# GSM_LED_Driver.net
KiCad netlist of a schematic drawn in Altium Designer
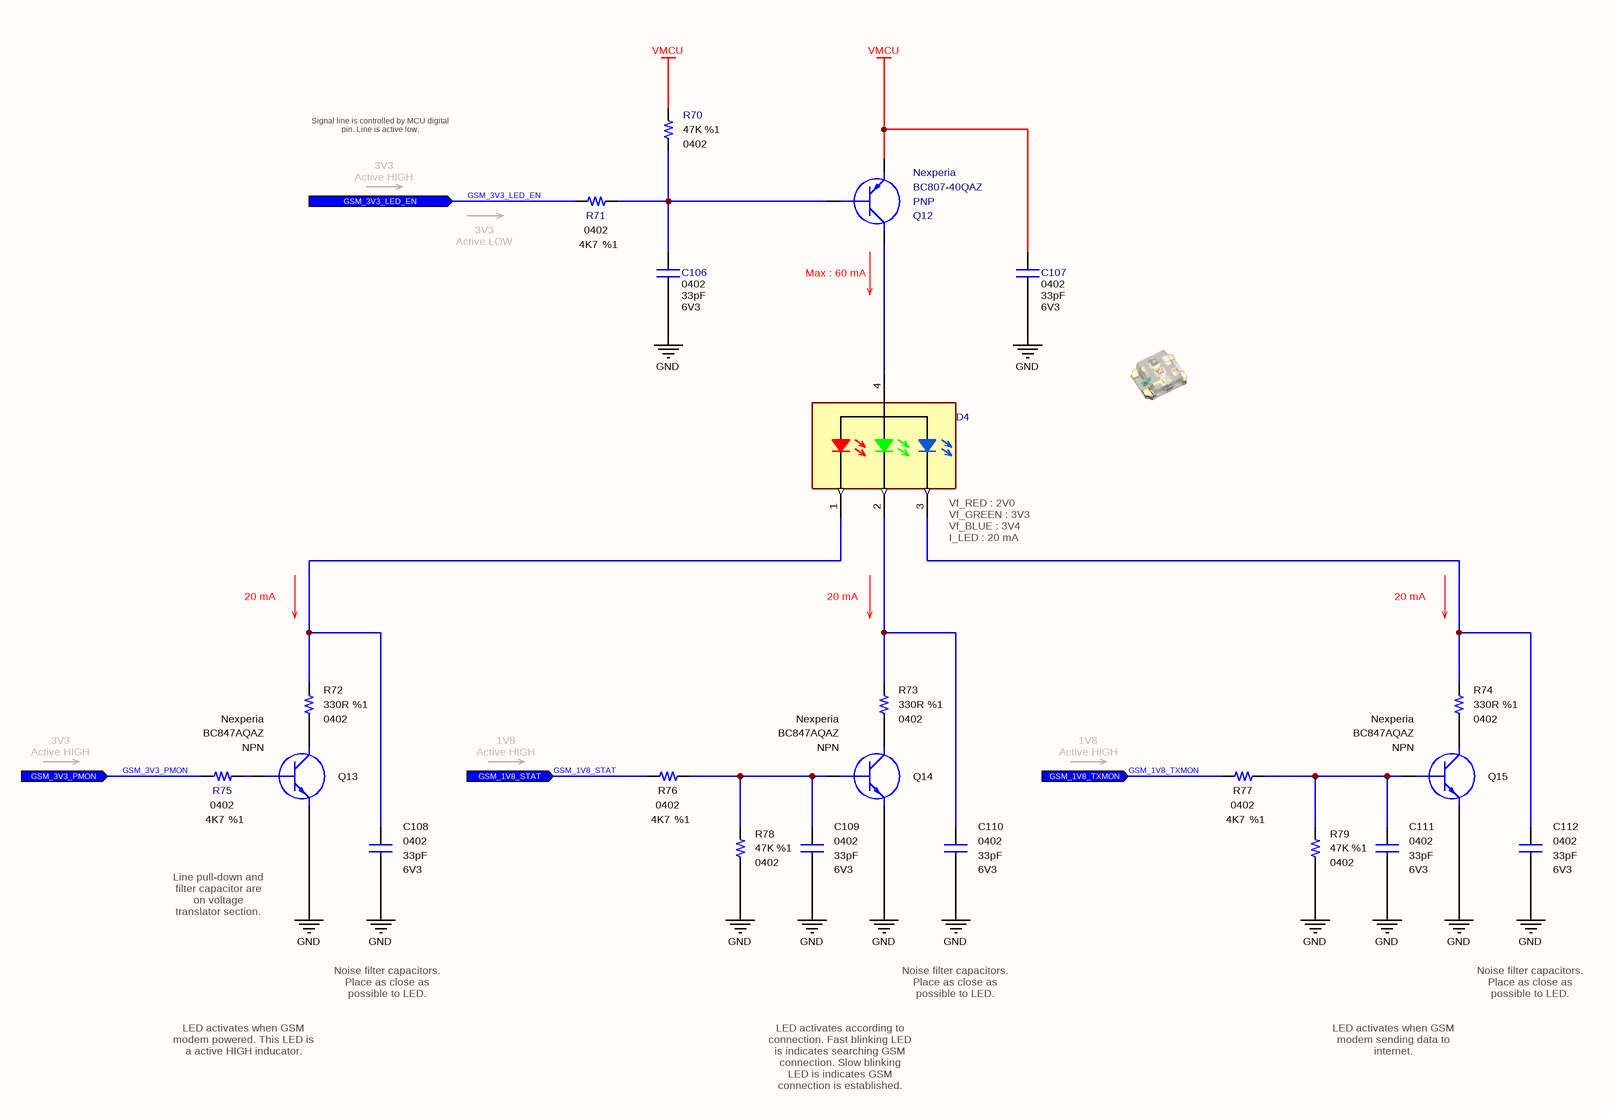
[diagram p0: GSM LED Driver.SchDoc]

(export (version "E")
  (design (tool "Eeschema 10.0.6"))
  (components
    (comp (ref "C106")
      (value "33pF")
      (footprint "CAPACITOR_0402")
      (description "Capacitor - 33pF [0402] (Ceramic)")
      (fields
        (field (name "CASE") "0402")
        (field (name "TOLERANCE") "10%")
        (field (name "VOLTAGE") "6V3")
        (field (name "MANUFACTURER PART NUMBER") "C0402C330J9RACAUTO")
      )
      (libsource (lib "Ovoo_Library") (part "Capacitor - 33pF [0402-6V3]"))
    )
    (comp (ref "C107")
      (value "33pF")
      (footprint "CAPACITOR_0402")
      (description "Capacitor - 33pF [0402] (Ceramic)")
      (fields
        (field (name "CASE") "0402")
        (field (name "TOLERANCE") "10%")
        (field (name "VOLTAGE") "6V3")
        (field (name "MANUFACTURER PART NUMBER") "C0402C330J9RACAUTO")
      )
      (libsource (lib "Ovoo_Library") (part "Capacitor - 33pF [0402-6V3]"))
    )
    (comp (ref "C108")
      (value "33pF")
      (footprint "CAPACITOR_0402")
      (description "Capacitor - 33pF [0402] (Ceramic)")
      (fields
        (field (name "CASE") "0402")
        (field (name "TOLERANCE") "10%")
        (field (name "VOLTAGE") "6V3")
        (field (name "MANUFACTURER PART NUMBER") "C0402C330J9RACAUTO")
      )
      (libsource (lib "Ovoo_Library") (part "Capacitor - 33pF [0402-6V3]"))
    )
    (comp (ref "C109")
      (value "33pF")
      (footprint "CAPACITOR_0402")
      (description "Capacitor - 33pF [0402] (Ceramic)")
      (fields
        (field (name "CASE") "0402")
        (field (name "TOLERANCE") "10%")
        (field (name "VOLTAGE") "6V3")
        (field (name "MANUFACTURER PART NUMBER") "C0402C330J9RACAUTO")
      )
      (libsource (lib "Ovoo_Library") (part "Capacitor - 33pF [0402-6V3]"))
    )
    (comp (ref "C110")
      (value "33pF")
      (footprint "CAPACITOR_0402")
      (description "Capacitor - 33pF [0402] (Ceramic)")
      (fields
        (field (name "CASE") "0402")
        (field (name "TOLERANCE") "10%")
        (field (name "VOLTAGE") "6V3")
        (field (name "MANUFACTURER PART NUMBER") "C0402C330J9RACAUTO")
      )
      (libsource (lib "Ovoo_Library") (part "Capacitor - 33pF [0402-6V3]"))
    )
    (comp (ref "C111")
      (value "33pF")
      (footprint "CAPACITOR_0402")
      (description "Capacitor - 33pF [0402] (Ceramic)")
      (fields
        (field (name "CASE") "0402")
        (field (name "TOLERANCE") "10%")
        (field (name "VOLTAGE") "6V3")
        (field (name "MANUFACTURER PART NUMBER") "C0402C330J9RACAUTO")
      )
      (libsource (lib "Ovoo_Library") (part "Capacitor - 33pF [0402-6V3]"))
    )
    (comp (ref "C112")
      (value "33pF")
      (footprint "CAPACITOR_0402")
      (description "Capacitor - 33pF [0402] (Ceramic)")
      (fields
        (field (name "CASE") "0402")
        (field (name "TOLERANCE") "10%")
        (field (name "VOLTAGE") "6V3")
        (field (name "MANUFACTURER PART NUMBER") "C0402C330J9RACAUTO")
      )
      (libsource (lib "Ovoo_Library") (part "Capacitor - 33pF [0402-6V3]"))
    )
    (comp (ref "D4")
      (value "150066M153000")
      (footprint "Wurth_0606")
      (description "Standard LEDs - SMD PICOLED series Red LED")
      (fields (field (name "MOUSER PART NUMBER") "710-150066M153000"))
      (libsource (lib "Ovoo_Library") (part "Diode - RGB LED (150066M153000)"))
    )
    (comp (ref "Q12")
      (value "Bipolar PNP Transistors")
      (footprint "SOT1215")
      (description "Bipolar Transistors - BJT 45 V, 500 mA PNP gen purpose transistors")
      (fields
        (field (name "MOUSER PART NUMBER") "771-BC807-40QAZ")
        (field (name "POLARITY") "PNP")
        (field (name "MANUFACTURER NAME") "Nexperia")
        (field (name "MANUFACTURER PART NUMBER") "BC807-40QAZ")
      )
      (libsource (lib "Ovoo_Library") (part "Transistor - BC807"))
    )
    (comp (ref "Q13")
      (value "BC847AQAZ")
      (footprint "SOT1215")
      (description "Bipolar NPN Transistors")
      (fields
        (field (name "POLARITY") "NPN")
        (field (name "MANUFACTURER NAME") "Nexperia")
        (field (name "MANUFACTURER PART NUMBER") "BC847AQAZ")
      )
      (libsource (lib "Ovoo_Library") (part "Transistor - BC847"))
    )
    (comp (ref "Q14")
      (value "BC847AQAZ")
      (footprint "SOT1215")
      (description "Bipolar NPN Transistors")
      (fields
        (field (name "POLARITY") "NPN")
        (field (name "MANUFACTURER NAME") "Nexperia")
        (field (name "MANUFACTURER PART NUMBER") "BC847AQAZ")
      )
      (libsource (lib "Ovoo_Library") (part "Transistor - BC847"))
    )
    (comp (ref "Q15")
      (value "BC847AQAZ")
      (footprint "SOT1215")
      (description "Bipolar NPN Transistors")
      (fields
        (field (name "POLARITY") "NPN")
        (field (name "MANUFACTURER NAME") "Nexperia")
        (field (name "MANUFACTURER PART NUMBER") "BC847AQAZ")
      )
      (libsource (lib "Ovoo_Library") (part "Transistor - BC847"))
    )
    (comp (ref "R70")
      (value "47K")
      (footprint "RESISTOR_0402")
      (description "Thick Film Resistors - SMD 1/16 W 47 Kohms 1%")
      (fields
        (field (name "TOLERANCE") "%1")
        (field (name "CASE") "0402")
        (field (name "MANUFACTURER PART NUMBER") "CRCW040247K0FKED")
        (field (name "Comment") "47K - 0402 - %1 - 1/16W")
      )
      (libsource (lib "Ovoo_Library") (part "Resistor - 47K"))
    )
    (comp (ref "R71")
      (value "4K7")
      (footprint "RESISTOR_0402")
      (description "Thick Film Resistors - SMD 1/16 W 4.7 Kohms 1%")
      (fields
        (field (name "MANUFACTURER PART NUMBER") "CRCW04024K70FKED")
        (field (name "MOUSER PART NUMBER") "71-CRCW0402-4.7K-E3")
        (field (name "TOLERANCE") "%1")
        (field (name "CASE") "0402")
      )
      (libsource (lib "Ovoo_Library") (part "Resistor - 4K7"))
    )
    (comp (ref "R72")
      (value "330R")
      (footprint "RESISTOR_0402")
      (description "Thick Film Resistors - SMD 1/16 W 330 Ohm 1%")
      (fields
        (field (name "MANUFACTURER PART NUMBER") "CRCW0402330RFKED")
        (field (name "MOUSER PART NUMBER") "71-CRCW0402-330-E3")
        (field (name "CASE") "0402")
        (field (name "TOLERANCE") "%1")
      )
      (libsource (lib "Ovoo_Library") (part "Resistor - 330R"))
    )
    (comp (ref "R73")
      (value "330R")
      (footprint "RESISTOR_0402")
      (description "Thick Film Resistors - SMD 1/16 W 330 Ohm 1%")
      (fields
        (field (name "MANUFACTURER PART NUMBER") "CRCW0402330RFKED")
        (field (name "MOUSER PART NUMBER") "71-CRCW0402-330-E3")
        (field (name "CASE") "0402")
        (field (name "TOLERANCE") "%1")
      )
      (libsource (lib "Ovoo_Library") (part "Resistor - 330R"))
    )
    (comp (ref "R74")
      (value "330R")
      (footprint "RESISTOR_0402")
      (description "Thick Film Resistors - SMD 1/16 W 330 Ohm 1%")
      (fields
        (field (name "MANUFACTURER PART NUMBER") "CRCW0402330RFKED")
        (field (name "MOUSER PART NUMBER") "71-CRCW0402-330-E3")
        (field (name "CASE") "0402")
        (field (name "TOLERANCE") "%1")
      )
      (libsource (lib "Ovoo_Library") (part "Resistor - 330R"))
    )
    (comp (ref "R75")
      (value "4K7")
      (footprint "RESISTOR_0402")
      (description "Thick Film Resistors - SMD 1/16 W 4.7 Kohms 1%")
      (fields
        (field (name "MANUFACTURER PART NUMBER") "CRCW04024K70FKED")
        (field (name "MOUSER PART NUMBER") "71-CRCW0402-4.7K-E3")
        (field (name "TOLERANCE") "%1")
        (field (name "CASE") "0402")
      )
      (libsource (lib "Ovoo_Library") (part "Resistor - 4K7"))
    )
    (comp (ref "R76")
      (value "4K7")
      (footprint "RESISTOR_0402")
      (description "Thick Film Resistors - SMD 1/16 W 4.7 Kohms 1%")
      (fields
        (field (name "MANUFACTURER PART NUMBER") "CRCW04024K70FKED")
        (field (name "MOUSER PART NUMBER") "71-CRCW0402-4.7K-E3")
        (field (name "TOLERANCE") "%1")
        (field (name "CASE") "0402")
      )
      (libsource (lib "Ovoo_Library") (part "Resistor - 4K7"))
    )
    (comp (ref "R77")
      (value "4K7")
      (footprint "RESISTOR_0402")
      (description "Thick Film Resistors - SMD 1/16 W 4.7 Kohms 1%")
      (fields
        (field (name "MANUFACTURER PART NUMBER") "CRCW04024K70FKED")
        (field (name "MOUSER PART NUMBER") "71-CRCW0402-4.7K-E3")
        (field (name "TOLERANCE") "%1")
        (field (name "CASE") "0402")
      )
      (libsource (lib "Ovoo_Library") (part "Resistor - 4K7"))
    )
    (comp (ref "R78")
      (value "47K")
      (footprint "RESISTOR_0402")
      (description "Thick Film Resistors - SMD 1/16 W 47 Kohms 1%")
      (fields
        (field (name "TOLERANCE") "%1")
        (field (name "CASE") "0402")
        (field (name "MANUFACTURER PART NUMBER") "CRCW040247K0FKED")
        (field (name "Comment") "47K - 0402 - %1 - 1/16W")
      )
      (libsource (lib "Ovoo_Library") (part "Resistor - 47K"))
    )
    (comp (ref "R79")
      (value "47K")
      (footprint "RESISTOR_0402")
      (description "Thick Film Resistors - SMD 1/16 W 47 Kohms 1%")
      (fields
        (field (name "TOLERANCE") "%1")
        (field (name "CASE") "0402")
        (field (name "MANUFACTURER PART NUMBER") "CRCW040247K0FKED")
        (field (name "Comment") "47K - 0402 - %1 - 1/16W")
      )
      (libsource (lib "Ovoo_Library") (part "Resistor - 47K"))
    )
  )
  (nets
    (net (code "1") (name "/GSM_1V8_STAT") (class "Default")
      (node (ref "R76") (pin "2") (pinfunction "2_2") (pintype "passive"))
    )
    (net (code "2") (name "/GSM_1V8_TXMON") (class "Default")
      (node (ref "R77") (pin "2") (pinfunction "2_2") (pintype "passive"))
    )
    (net (code "3") (name "/GSM_3V3_LED_EN") (class "Default")
      (node (ref "R71") (pin "2") (pinfunction "2_2") (pintype "passive"))
    )
    (net (code "4") (name "/GSM_3V3_PMON") (class "Default")
      (node (ref "R75") (pin "2") (pinfunction "2_2") (pintype "passive"))
    )
    (net (code "5") (name "GND") (class "Default")
      (node (ref "C106") (pin "2") (pinfunction "2_2") (pintype "passive"))
      (node (ref "C107") (pin "2") (pinfunction "2_2") (pintype "passive"))
      (node (ref "C108") (pin "2") (pinfunction "2_2") (pintype "passive"))
      (node (ref "C109") (pin "2") (pinfunction "2_2") (pintype "passive"))
      (node (ref "C110") (pin "2") (pinfunction "2_2") (pintype "passive"))
      (node (ref "C111") (pin "2") (pinfunction "2_2") (pintype "passive"))
      (node (ref "C112") (pin "2") (pinfunction "2_2") (pintype "passive"))
      (node (ref "Q13") (pin "2") (pinfunction "E_2") (pintype "passive"))
      (node (ref "Q14") (pin "2") (pinfunction "E_2") (pintype "passive"))
      (node (ref "Q15") (pin "2") (pinfunction "E_2") (pintype "passive"))
      (node (ref "R78") (pin "1") (pinfunction "1_1") (pintype "passive"))
      (node (ref "R79") (pin "1") (pinfunction "1_1") (pintype "passive"))
    )
    (net (code "6") (name "Net-(C108-Pad1)") (class "Default")
      (node (ref "C108") (pin "1") (pinfunction "1_1") (pintype "passive"))
      (node (ref "D4") (pin "1") (pinfunction "1_1") (pintype "output"))
      (node (ref "R72") (pin "2") (pinfunction "2_2") (pintype "passive"))
    )
    (net (code "7") (name "Net-(C110-Pad1)") (class "Default")
      (node (ref "C110") (pin "1") (pinfunction "1_1") (pintype "passive"))
      (node (ref "D4") (pin "2") (pinfunction "2_2") (pintype "output"))
      (node (ref "R73") (pin "2") (pinfunction "2_2") (pintype "passive"))
    )
    (net (code "8") (name "Net-(C112-Pad1)") (class "Default")
      (node (ref "C112") (pin "1") (pinfunction "1_1") (pintype "passive"))
      (node (ref "D4") (pin "3") (pinfunction "3_3") (pintype "output"))
      (node (ref "R74") (pin "2") (pinfunction "2_2") (pintype "passive"))
    )
    (net (code "9") (name "Net-(Q12-B)") (class "Default")
      (node (ref "C106") (pin "1") (pinfunction "1_1") (pintype "passive"))
      (node (ref "Q12") (pin "1") (pinfunction "B_1") (pintype "passive"))
      (node (ref "R70") (pin "1") (pinfunction "1_1") (pintype "passive"))
      (node (ref "R71") (pin "1") (pinfunction "1_1") (pintype "passive"))
    )
    (net (code "10") (name "Net-(Q12-C)") (class "Default")
      (node (ref "D4") (pin "4") (pinfunction "4_4") (pintype "power_in"))
      (node (ref "Q12") (pin "3") (pinfunction "C_3") (pintype "passive"))
    )
    (net (code "11") (name "Net-(Q13-B)") (class "Default")
      (node (ref "Q13") (pin "1") (pinfunction "B_1") (pintype "passive"))
      (node (ref "R75") (pin "1") (pinfunction "1_1") (pintype "passive"))
    )
    (net (code "12") (name "Net-(Q13-C)") (class "Default")
      (node (ref "Q13") (pin "3") (pinfunction "C_3") (pintype "passive"))
      (node (ref "R72") (pin "1") (pinfunction "1_1") (pintype "passive"))
    )
    (net (code "13") (name "Net-(Q14-B)") (class "Default")
      (node (ref "C109") (pin "1") (pinfunction "1_1") (pintype "passive"))
      (node (ref "Q14") (pin "1") (pinfunction "B_1") (pintype "passive"))
      (node (ref "R76") (pin "1") (pinfunction "1_1") (pintype "passive"))
      (node (ref "R78") (pin "2") (pinfunction "2_2") (pintype "passive"))
    )
    (net (code "14") (name "Net-(Q14-C)") (class "Default")
      (node (ref "Q14") (pin "3") (pinfunction "C_3") (pintype "passive"))
      (node (ref "R73") (pin "1") (pinfunction "1_1") (pintype "passive"))
    )
    (net (code "15") (name "Net-(Q15-B)") (class "Default")
      (node (ref "C111") (pin "1") (pinfunction "1_1") (pintype "passive"))
      (node (ref "Q15") (pin "1") (pinfunction "B_1") (pintype "passive"))
      (node (ref "R77") (pin "1") (pinfunction "1_1") (pintype "passive"))
      (node (ref "R79") (pin "2") (pinfunction "2_2") (pintype "passive"))
    )
    (net (code "16") (name "Net-(Q15-C)") (class "Default")
      (node (ref "Q15") (pin "3") (pinfunction "C_3") (pintype "passive"))
      (node (ref "R74") (pin "1") (pinfunction "1_1") (pintype "passive"))
    )
    (net (code "17") (name "VMCU") (class "Default")
      (node (ref "C107") (pin "1") (pinfunction "1_1") (pintype "passive"))
      (node (ref "Q12") (pin "2") (pinfunction "E_2") (pintype "passive"))
      (node (ref "R70") (pin "2") (pinfunction "2_2") (pintype "passive"))
    )
  )
)
